# Front_Node_MiniLock_SMD_Rs.net
KiCad netlist of a schematic drawn in EAGLE
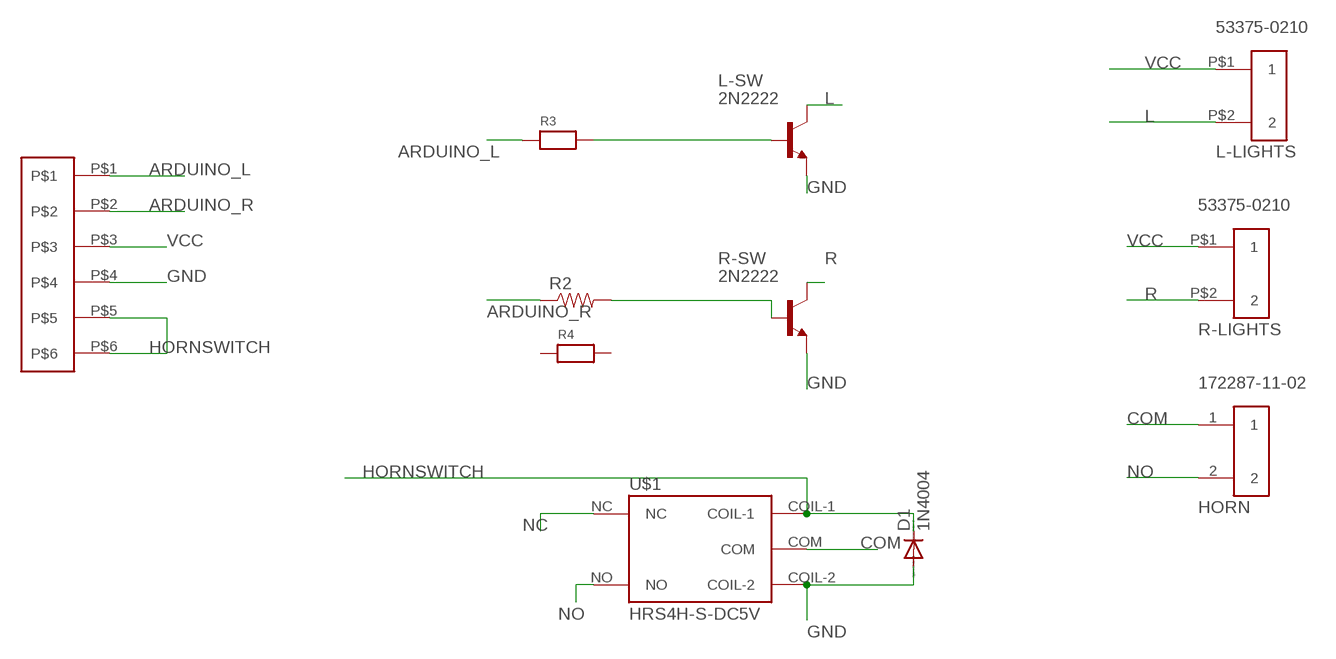
[diagram p0: schematic, sheet 1]

(export (version "E")
  (design (tool "Eeschema 10.0.6"))
  (components
    (comp (ref "ARDUINO")
      (value "53375-0610")
      (footprint "eagle-import:53375-0610-MINI-LOCK")
      (libsource (lib "eagle-import") (part "53375-0610"))
    )
    (comp (ref "D1")
      (value "1N4004")
      (footprint "eagle-import:DO41-10")
      (libsource (lib "eagle-import") (part "1N4004"))
    )
    (comp (ref "HORN")
      (value "172287-11-02")
      (footprint "eagle-import:172287-ULTRA-FIT")
      (libsource (lib "eagle-import") (part "172287-11-02"))
    )
    (comp (ref "L-LIGHTS")
      (value "53375-0210")
      (footprint "eagle-import:53375-0210-MINI-LOCK")
      (libsource (lib "eagle-import") (part "53375-0210"))
    )
    (comp (ref "L-SW")
      (value "2N2222")
      (footprint "eagle-import:TO18")
      (libsource (lib "eagle-import") (part "2N2222"))
    )
    (comp (ref "R-LIGHTS")
      (value "53375-0210")
      (footprint "eagle-import:53375-0210-MINI-LOCK")
      (libsource (lib "eagle-import") (part "53375-0210"))
    )
    (comp (ref "R-SW")
      (value "2N2222")
      (footprint "eagle-import:TO18")
      (libsource (lib "eagle-import") (part "2N2222"))
    )
    (comp (ref "R2")
      (value "RESISTORPTH-1/4W")
      (footprint "eagle-import:AXIAL-0.4")
      (libsource (lib "eagle-import") (part "RESISTORPTH-1/4W"))
    )
    (comp (ref "R3")
      (value "RESISTOR1206")
      (footprint "eagle-import:1206")
      (libsource (lib "eagle-import") (part "microbuilder_RESISTOR1206"))
    )
    (comp (ref "R4")
      (value "RESISTOR1206")
      (footprint "eagle-import:1206")
      (libsource (lib "eagle-import") (part "microbuilder_RESISTOR1206"))
    )
    (comp (ref "U$1")
      (value "HRS4H-S-DC5V")
      (footprint "eagle-import:RELAY")
      (libsource (lib "eagle-import") (part "HRS4H-S-DC5V"))
    )
  )
  (nets
    (net (code "1") (name "/ARDUINO_L") (class "Default")
      (node (ref "ARDUINO") (pin "P$1") (pinfunction "P$1_P$1") (pintype "bidirectional"))
      (node (ref "R3") (pin "1") (pinfunction "1_1") (pintype "passive"))
    )
    (net (code "2") (name "/ARDUINO_R") (class "Default")
      (node (ref "ARDUINO") (pin "P$2") (pinfunction "P$2_P$2") (pintype "bidirectional"))
      (node (ref "R2") (pin "P$1") (pinfunction "1_P$1") (pintype "passive"))
    )
    (net (code "3") (name "/COM") (class "Default")
      (node (ref "HORN") (pin "1") (pinfunction "1_1") (pintype "bidirectional"))
      (node (ref "U$1") (pin "COM") (pinfunction "COM_COM") (pintype "bidirectional"))
    )
    (net (code "4") (name "/GND") (class "Default")
      (node (ref "ARDUINO") (pin "P$4") (pinfunction "P$4_P$4") (pintype "bidirectional"))
      (node (ref "D1") (pin "A") (pinfunction "A_A") (pintype "passive"))
      (node (ref "L-SW") (pin "1") (pinfunction "E_1") (pintype "passive"))
      (node (ref "R-SW") (pin "1") (pinfunction "E_1") (pintype "passive"))
      (node (ref "U$1") (pin "COIL-2") (pinfunction "COIL-2_COIL-2") (pintype "power_in"))
    )
    (net (code "5") (name "/HORNSWITCH") (class "Default")
      (node (ref "ARDUINO") (pin "P$5") (pinfunction "P$5_P$5") (pintype "bidirectional"))
      (node (ref "ARDUINO") (pin "P$6") (pinfunction "P$6_P$6") (pintype "bidirectional"))
      (node (ref "D1") (pin "C") (pinfunction "C_C") (pintype "passive"))
      (node (ref "U$1") (pin "COIL-1") (pinfunction "COIL-1_COIL-1") (pintype "power_in"))
    )
    (net (code "6") (name "/L") (class "Default")
      (node (ref "L-LIGHTS") (pin "P$2") (pinfunction "2_P$2") (pintype "bidirectional"))
      (node (ref "L-SW") (pin "3") (pinfunction "C_3") (pintype "passive"))
    )
    (net (code "7") (name "/NC") (class "Default")
      (node (ref "U$1") (pin "NC") (pinfunction "NC_NC") (pintype "bidirectional"))
    )
    (net (code "8") (name "/NO") (class "Default")
      (node (ref "HORN") (pin "2") (pinfunction "2_2") (pintype "bidirectional"))
      (node (ref "U$1") (pin "NO") (pinfunction "NO_NO") (pintype "bidirectional"))
    )
    (net (code "9") (name "/R") (class "Default")
      (node (ref "R-LIGHTS") (pin "P$2") (pinfunction "2_P$2") (pintype "bidirectional"))
      (node (ref "R-SW") (pin "3") (pinfunction "C_3") (pintype "passive"))
    )
    (net (code "10") (name "/VCC") (class "Default")
      (node (ref "ARDUINO") (pin "P$3") (pinfunction "P$3_P$3") (pintype "bidirectional"))
      (node (ref "L-LIGHTS") (pin "P$1") (pinfunction "1_P$1") (pintype "bidirectional"))
      (node (ref "R-LIGHTS") (pin "P$1") (pinfunction "1_P$1") (pintype "bidirectional"))
    )
    (net (code "11") (name "Net-(L-SW-B)") (class "Default")
      (node (ref "L-SW") (pin "2") (pinfunction "B_2") (pintype "passive"))
      (node (ref "R3") (pin "2") (pinfunction "2_2") (pintype "passive"))
    )
    (net (code "12") (name "Net-(R-SW-B)") (class "Default")
      (node (ref "R-SW") (pin "2") (pinfunction "B_2") (pintype "passive"))
      (node (ref "R2") (pin "P$2") (pinfunction "2_P$2") (pintype "passive"))
    )
    (net (code "13") (name "unconnected-(R4-Pad1)") (class "Default")
      (node (ref "R4") (pin "1") (pinfunction "1_1") (pintype "passive"))
    )
    (net (code "14") (name "unconnected-(R4-Pad2)") (class "Default")
      (node (ref "R4") (pin "2") (pinfunction "2_2") (pintype "passive"))
    )
  )
)
